# cw312_xc7a35t_cardedge.net
KiCad netlist of a schematic drawn in Altium Designer
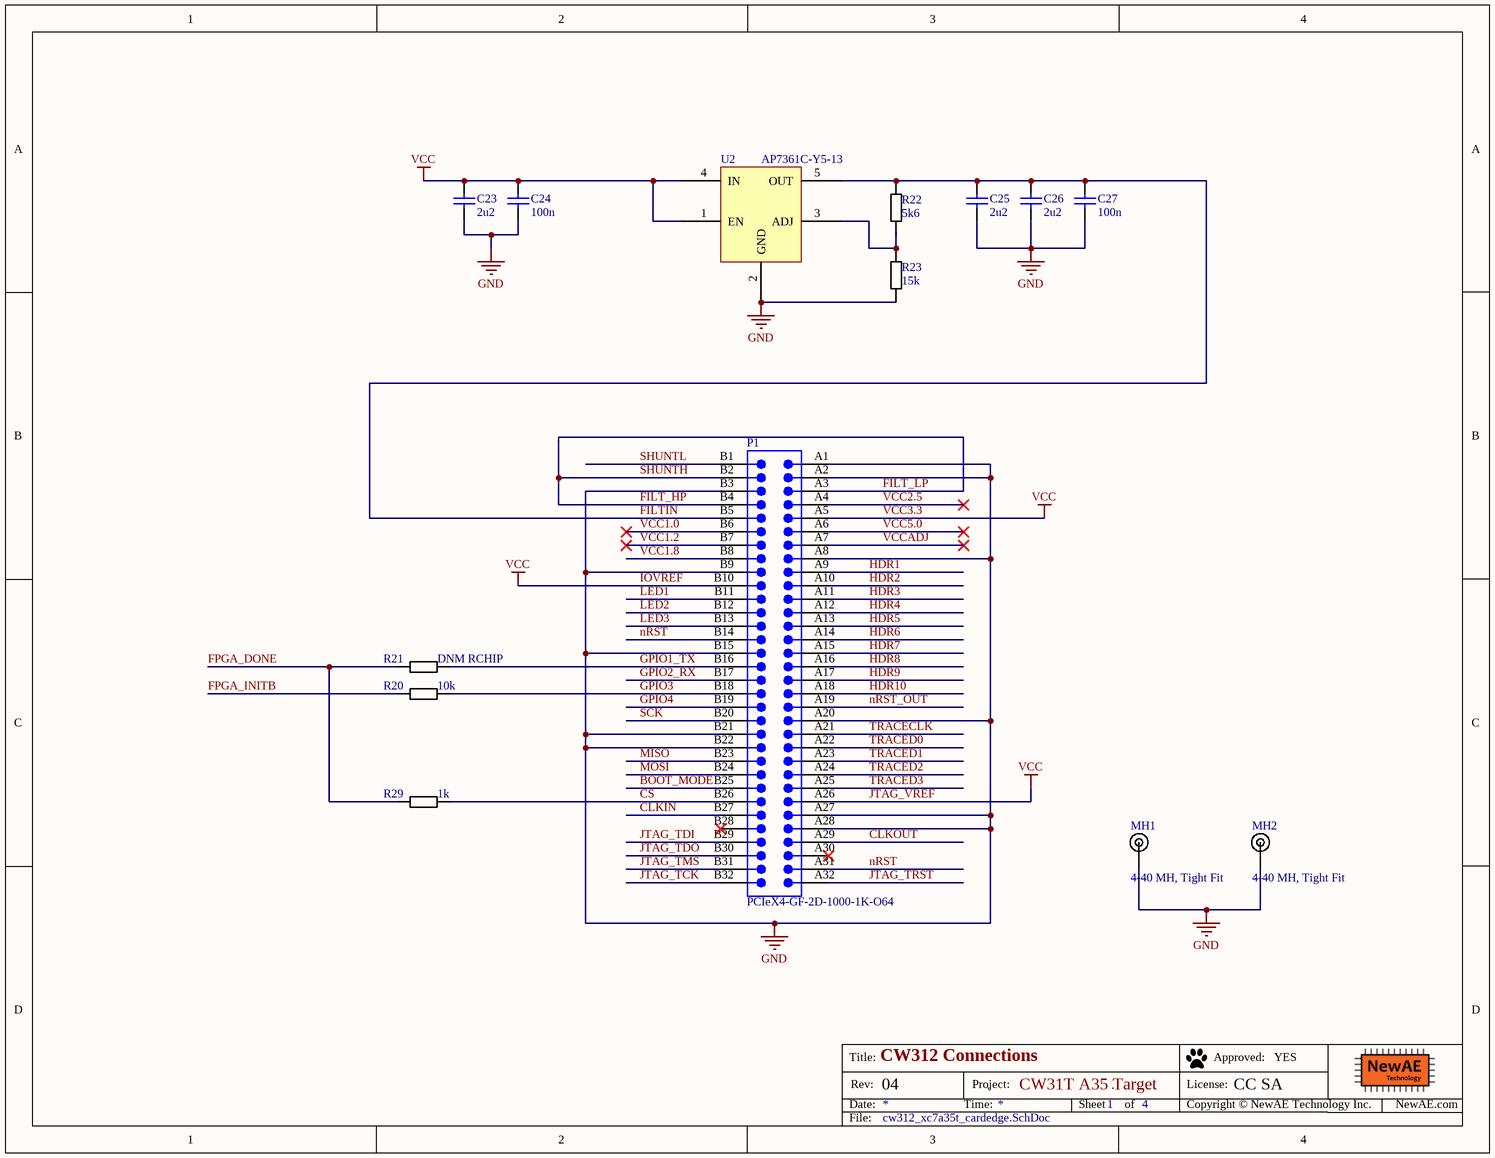
[diagram p0: cw312_xc7a35t_cardedge.SchDoc]

(export (version "E")
  (design (tool "Eeschema 10.0.6"))
  (components
    (comp (ref "C23")
      (value "2u2")
      (footprint "CAPC0603_M")
      (description "2u2, 0603")
      (fields (field (name "PART NUMBER") "CCHIP-2u2-0603"))
      (libsource (lib "NewAE_AltiumLib") (part "CAP"))
    )
    (comp (ref "C24")
      (value "100n")
      (footprint "CAPC0402_M")
      (description "100n, 0402")
      (fields (field (name "PART NUMBER") "CCHIP-100n-0402"))
      (libsource (lib "NewAE_AltiumLib") (part "CAP"))
    )
    (comp (ref "C25")
      (value "2u2")
      (footprint "CAPC0603_M")
      (description "2u2, 0603")
      (fields (field (name "PART NUMBER") "CCHIP-2u2-0603"))
      (libsource (lib "NewAE_AltiumLib") (part "CAP"))
    )
    (comp (ref "C26")
      (value "2u2")
      (footprint "CAPC0603_M")
      (description "2u2, 0603")
      (fields (field (name "PART NUMBER") "CCHIP-2u2-0603"))
      (libsource (lib "NewAE_AltiumLib") (part "CAP"))
    )
    (comp (ref "C27")
      (value "100n")
      (footprint "CAPC0402_M")
      (description "100n, 0402")
      (fields (field (name "PART NUMBER") "CCHIP-100n-0402"))
      (libsource (lib "NewAE_AltiumLib") (part "CAP"))
    )
    (comp (ref "MH1")
      (value "4-40 MH, Tight Fit")
      (footprint "MOUNT_#4_TIGHT")
      (description "Machine screw 4-40 Mounting Hole")
      (fields (field (name "PART NUMBER") "MOUNT_#4_TIGHT"))
      (libsource (lib "NewAE_AltiumLib") (part "Mounting_Hole"))
    )
    (comp (ref "MH2")
      (value "4-40 MH, Tight Fit")
      (footprint "MOUNT_#4_TIGHT")
      (description "Machine screw 4-40 Mounting Hole")
      (fields (field (name "PART NUMBER") "MOUNT_#4_TIGHT"))
      (libsource (lib "NewAE_AltiumLib") (part "Mounting_Hole"))
    )
    (comp (ref "P1")
      (value "PCIeX4-GF-2D-1000-1K-O64")
      (footprint "PCIeX4-GF-2D-1000-1K-O64")
      (description "Golden finger, PCIeX4, Dual, Opposite, Pitch 1mm, 64-Position")
      (fields (field (name "PUBLISHER") "Altium"))
      (libsource (lib "Altium Content Vault") (part "PCIeX4-GF-2D-1000-1K-O64"))
    )
    (comp (ref "R20")
      (value "10k")
      (footprint "RESC1608X55N")
      (description "10k res, 0603, 1%, 1/10W")
      (fields (field (name "PART NUMBER") "RCHIP-10K-0603") (field (name "TOLERANCE") "1%"))
      (libsource (lib "") (part "RES-EU_1"))
    )
    (comp (ref "R21")
      (value "DNM RCHIP")
      (footprint "RESC1608X55N")
      (description "Do Not Mount Resistor")
      (fields (field (name "PART NUMBER") "RCHIP-DNM-0603"))
      (libsource (lib "") (part "RES-EU_1"))
    )
    (comp (ref "R22")
      (value "5k6")
      (footprint "RESC1608X55N")
      (description "5k6 res, 0603, 1%, 1/10W")
      (fields (field (name "PART NUMBER") "RCHIP-5K6-0603") (field (name "TOLERANCE") "1%"))
      (libsource (lib "NewAE_AltiumLib") (part "RES-EU"))
    )
    (comp (ref "R23")
      (value "15k")
      (footprint "RESC1608X55N")
      (description "15k res, 0603, 1%, 1/10W")
      (fields (field (name "PART NUMBER") "RCHIP-15K-0603") (field (name "TOLERANCE") "1%"))
      (libsource (lib "NewAE_AltiumLib") (part "RES-EU"))
    )
    (comp (ref "R29")
      (value "1k")
      (footprint "RESC1608X55N")
      (description "1k res, 0603, 1%, 1/10W")
      (fields (field (name "PART NUMBER") "RCHIP-1K-0603") (field (name "TOLERANCE") "1%"))
      (libsource (lib "") (part "RES-EU_1"))
    )
    (comp (ref "U2")
      (value "AP7361C-Y5-13")
      (footprint "SOT89-5")
      (description "Regulator, Adj, LDO, 1A")
      (libsource (lib "NewAE_AltiumLib") (part "AP7361C-Y5-13"))
    )
  )
  (nets
    (net (code "1") (name "/BOOT_MODE") (class "Default")
      (node (ref "P1") (pin "B25") (pinfunction "B25_B25") (pintype "passive"))
    )
    (net (code "2") (name "/CLKIN") (class "Default")
      (node (ref "P1") (pin "B27") (pinfunction "B27_B27") (pintype "passive"))
    )
    (net (code "3") (name "/CLKOUT") (class "Default")
      (node (ref "P1") (pin "A29") (pinfunction "A29_A29") (pintype "passive"))
    )
    (net (code "4") (name "/CS") (class "Default")
      (node (ref "P1") (pin "B26") (pinfunction "B26_B26") (pintype "passive"))
      (node (ref "R29") (pin "2") (pinfunction "2_2") (pintype "passive"))
    )
    (net (code "5") (name "/FILTIN") (class "Default")
      (node (ref "C25") (pin "1") (pinfunction "1_1") (pintype "passive"))
      (node (ref "C26") (pin "1") (pinfunction "1_1") (pintype "passive"))
      (node (ref "C27") (pin "1") (pinfunction "1_1") (pintype "passive"))
      (node (ref "P1") (pin "B5") (pinfunction "B5_B5") (pintype "passive"))
      (node (ref "R22") (pin "1") (pinfunction "1_1") (pintype "passive"))
      (node (ref "U2") (pin "5") (pinfunction "OUT_5") (pintype "passive"))
    )
    (net (code "6") (name "/FILT_HP") (class "Default")
      (node (ref "P1") (pin "A3") (pinfunction "A3_A3") (pintype "passive"))
      (node (ref "P1") (pin "B2") (pinfunction "B2_B2") (pintype "passive"))
      (node (ref "P1") (pin "B4") (pinfunction "B4_B4") (pintype "passive"))
    )
    (net (code "7") (name "/FPGA_DONE") (class "Default")
      (node (ref "R21") (pin "1") (pinfunction "1_1") (pintype "passive"))
      (node (ref "R29") (pin "1") (pinfunction "1_1") (pintype "passive"))
    )
    (net (code "8") (name "/FPGA_INITB") (class "Default")
      (node (ref "R20") (pin "1") (pinfunction "1_1") (pintype "passive"))
    )
    (net (code "9") (name "/GPIO1_TX") (class "Default")
      (node (ref "P1") (pin "B16") (pinfunction "B16_B16") (pintype "passive"))
      (node (ref "R21") (pin "2") (pinfunction "2_2") (pintype "passive"))
    )
    (net (code "10") (name "/GPIO2_RX") (class "Default")
      (node (ref "P1") (pin "B17") (pinfunction "B17_B17") (pintype "passive"))
    )
    (net (code "11") (name "/GPIO3") (class "Default")
      (node (ref "P1") (pin "B18") (pinfunction "B18_B18") (pintype "passive"))
      (node (ref "R20") (pin "2") (pinfunction "2_2") (pintype "passive"))
    )
    (net (code "12") (name "/GPIO4") (class "Default")
      (node (ref "P1") (pin "B19") (pinfunction "B19_B19") (pintype "passive"))
    )
    (net (code "13") (name "/HDR1") (class "Default")
      (node (ref "P1") (pin "A9") (pinfunction "A9_A9") (pintype "passive"))
    )
    (net (code "14") (name "/HDR2") (class "Default")
      (node (ref "P1") (pin "A10") (pinfunction "A10_A10") (pintype "passive"))
    )
    (net (code "15") (name "/HDR3") (class "Default")
      (node (ref "P1") (pin "A11") (pinfunction "A11_A11") (pintype "passive"))
    )
    (net (code "16") (name "/HDR4") (class "Default")
      (node (ref "P1") (pin "A12") (pinfunction "A12_A12") (pintype "passive"))
    )
    (net (code "17") (name "/HDR5") (class "Default")
      (node (ref "P1") (pin "A13") (pinfunction "A13_A13") (pintype "passive"))
    )
    (net (code "18") (name "/HDR6") (class "Default")
      (node (ref "P1") (pin "A14") (pinfunction "A14_A14") (pintype "passive"))
    )
    (net (code "19") (name "/HDR7") (class "Default")
      (node (ref "P1") (pin "A15") (pinfunction "A15_A15") (pintype "passive"))
    )
    (net (code "20") (name "/HDR8") (class "Default")
      (node (ref "P1") (pin "A16") (pinfunction "A16_A16") (pintype "passive"))
    )
    (net (code "21") (name "/HDR9") (class "Default")
      (node (ref "P1") (pin "A17") (pinfunction "A17_A17") (pintype "passive"))
    )
    (net (code "22") (name "/HDR10") (class "Default")
      (node (ref "P1") (pin "A18") (pinfunction "A18_A18") (pintype "passive"))
    )
    (net (code "23") (name "/JTAG_TCK") (class "Default")
      (node (ref "P1") (pin "B32") (pinfunction "B32_B32") (pintype "passive"))
    )
    (net (code "24") (name "/JTAG_TDI") (class "Default")
      (node (ref "P1") (pin "B29") (pinfunction "B29_B29") (pintype "passive"))
    )
    (net (code "25") (name "/JTAG_TDO") (class "Default")
      (node (ref "P1") (pin "B30") (pinfunction "B30_B30") (pintype "passive"))
    )
    (net (code "26") (name "/JTAG_TMS") (class "Default")
      (node (ref "P1") (pin "B31") (pinfunction "B31_B31") (pintype "passive"))
    )
    (net (code "27") (name "/JTAG_TRST") (class "Default")
      (node (ref "P1") (pin "A32") (pinfunction "A32_A32") (pintype "passive"))
    )
    (net (code "28") (name "/LED1") (class "Default")
      (node (ref "P1") (pin "B11") (pinfunction "B11_B11") (pintype "passive"))
    )
    (net (code "29") (name "/LED2") (class "Default")
      (node (ref "P1") (pin "B12") (pinfunction "B12_B12") (pintype "passive"))
    )
    (net (code "30") (name "/LED3") (class "Default")
      (node (ref "P1") (pin "B13") (pinfunction "B13_B13") (pintype "passive"))
    )
    (net (code "31") (name "/MISO") (class "Default")
      (node (ref "P1") (pin "B23") (pinfunction "B23_B23") (pintype "passive"))
    )
    (net (code "32") (name "/MOSI") (class "Default")
      (node (ref "P1") (pin "B24") (pinfunction "B24_B24") (pintype "passive"))
    )
    (net (code "33") (name "/SCK") (class "Default")
      (node (ref "P1") (pin "B20") (pinfunction "B20_B20") (pintype "passive"))
    )
    (net (code "34") (name "/SHUNTL") (class "Default")
      (node (ref "P1") (pin "B1") (pinfunction "B1_B1") (pintype "passive"))
    )
    (net (code "35") (name "/TRACECLK") (class "Default")
      (node (ref "P1") (pin "A21") (pinfunction "A21_A21") (pintype "passive"))
    )
    (net (code "36") (name "/TRACED0") (class "Default")
      (node (ref "P1") (pin "A22") (pinfunction "A22_A22") (pintype "passive"))
    )
    (net (code "37") (name "/TRACED1") (class "Default")
      (node (ref "P1") (pin "A23") (pinfunction "A23_A23") (pintype "passive"))
    )
    (net (code "38") (name "/TRACED2") (class "Default")
      (node (ref "P1") (pin "A24") (pinfunction "A24_A24") (pintype "passive"))
    )
    (net (code "39") (name "/TRACED3") (class "Default")
      (node (ref "P1") (pin "A25") (pinfunction "A25_A25") (pintype "passive"))
    )
    (net (code "40") (name "/VCC1.0") (class "Default")
      (node (ref "P1") (pin "B6") (pinfunction "B6_B6") (pintype "passive+no_connect"))
    )
    (net (code "41") (name "/VCC1.2") (class "Default")
      (node (ref "P1") (pin "B7") (pinfunction "B7_B7") (pintype "passive+no_connect"))
    )
    (net (code "42") (name "/VCC1.8") (class "Default")
      (node (ref "P1") (pin "B8") (pinfunction "B8_B8") (pintype "passive"))
    )
    (net (code "43") (name "/VCC2.5") (class "Default")
      (node (ref "P1") (pin "A4") (pinfunction "A4_A4") (pintype "passive+no_connect"))
    )
    (net (code "44") (name "/VCC5.0") (class "Default")
      (node (ref "P1") (pin "A6") (pinfunction "A6_A6") (pintype "passive+no_connect"))
    )
    (net (code "45") (name "/VCCADJ") (class "Default")
      (node (ref "P1") (pin "A7") (pinfunction "A7_A7") (pintype "passive+no_connect"))
    )
    (net (code "46") (name "/nRST") (class "Default")
      (node (ref "P1") (pin "A31") (pinfunction "A31_A31") (pintype "passive"))
      (node (ref "P1") (pin "B14") (pinfunction "B14_B14") (pintype "passive"))
    )
    (net (code "47") (name "/nRST_OUT") (class "Default")
      (node (ref "P1") (pin "A19") (pinfunction "A19_A19") (pintype "passive"))
    )
    (net (code "48") (name "GND") (class "Default")
      (node (ref "C23") (pin "2") (pinfunction "2_2") (pintype "passive"))
      (node (ref "C24") (pin "2") (pinfunction "2_2") (pintype "passive"))
      (node (ref "C25") (pin "2") (pinfunction "2_2") (pintype "passive"))
      (node (ref "C26") (pin "2") (pinfunction "2_2") (pintype "passive"))
      (node (ref "C27") (pin "2") (pinfunction "2_2") (pintype "passive"))
      (node (ref "MH1") (pin "1") (pinfunction "1_1") (pintype "passive"))
      (node (ref "MH2") (pin "1") (pinfunction "1_1") (pintype "passive"))
      (node (ref "P1") (pin "A1") (pinfunction "A1_A1") (pintype "passive"))
      (node (ref "P1") (pin "A2") (pinfunction "A2_A2") (pintype "passive"))
      (node (ref "P1") (pin "A20") (pinfunction "A20_A20") (pintype "passive"))
      (node (ref "P1") (pin "A27") (pinfunction "A27_A27") (pintype "passive"))
      (node (ref "P1") (pin "A28") (pinfunction "A28_A28") (pintype "passive"))
      (node (ref "P1") (pin "A8") (pinfunction "A8_A8") (pintype "passive"))
      (node (ref "P1") (pin "B15") (pinfunction "B15_B15") (pintype "passive"))
      (node (ref "P1") (pin "B21") (pinfunction "B21_B21") (pintype "passive"))
      (node (ref "P1") (pin "B22") (pinfunction "B22_B22") (pintype "passive"))
      (node (ref "P1") (pin "B3") (pinfunction "B3_B3") (pintype "passive"))
      (node (ref "P1") (pin "B9") (pinfunction "B9_B9") (pintype "passive"))
      (node (ref "R23") (pin "2") (pinfunction "2_2") (pintype "passive"))
      (node (ref "U2") (pin "2") (pinfunction "GND_2") (pintype "passive"))
    )
    (net (code "49") (name "Net-(U2-ADJ)") (class "Default")
      (node (ref "R22") (pin "2") (pinfunction "2_2") (pintype "passive"))
      (node (ref "R23") (pin "1") (pinfunction "1_1") (pintype "passive"))
      (node (ref "U2") (pin "3") (pinfunction "ADJ_3") (pintype "passive"))
    )
    (net (code "50") (name "VCC") (class "Default")
      (node (ref "C23") (pin "1") (pinfunction "1_1") (pintype "passive"))
      (node (ref "C24") (pin "1") (pinfunction "1_1") (pintype "passive"))
      (node (ref "P1") (pin "A26") (pinfunction "A26_A26") (pintype "passive"))
      (node (ref "P1") (pin "A5") (pinfunction "A5_A5") (pintype "passive"))
      (node (ref "P1") (pin "B10") (pinfunction "B10_B10") (pintype "passive"))
      (node (ref "U2") (pin "1") (pinfunction "EN_1") (pintype "passive"))
      (node (ref "U2") (pin "4") (pinfunction "IN_4") (pintype "passive"))
    )
    (net (code "51") (name "unconnected-(P1-PadA30)") (class "Default")
      (node (ref "P1") (pin "A30") (pinfunction "A30_A30") (pintype "passive+no_connect"))
    )
    (net (code "52") (name "unconnected-(P1-PadB28)") (class "Default")
      (node (ref "P1") (pin "B28") (pinfunction "B28_B28") (pintype "passive+no_connect"))
    )
  )
)
